# Spannungsversorgung_V2.net
KiCad netlist of a schematic drawn in EAGLE
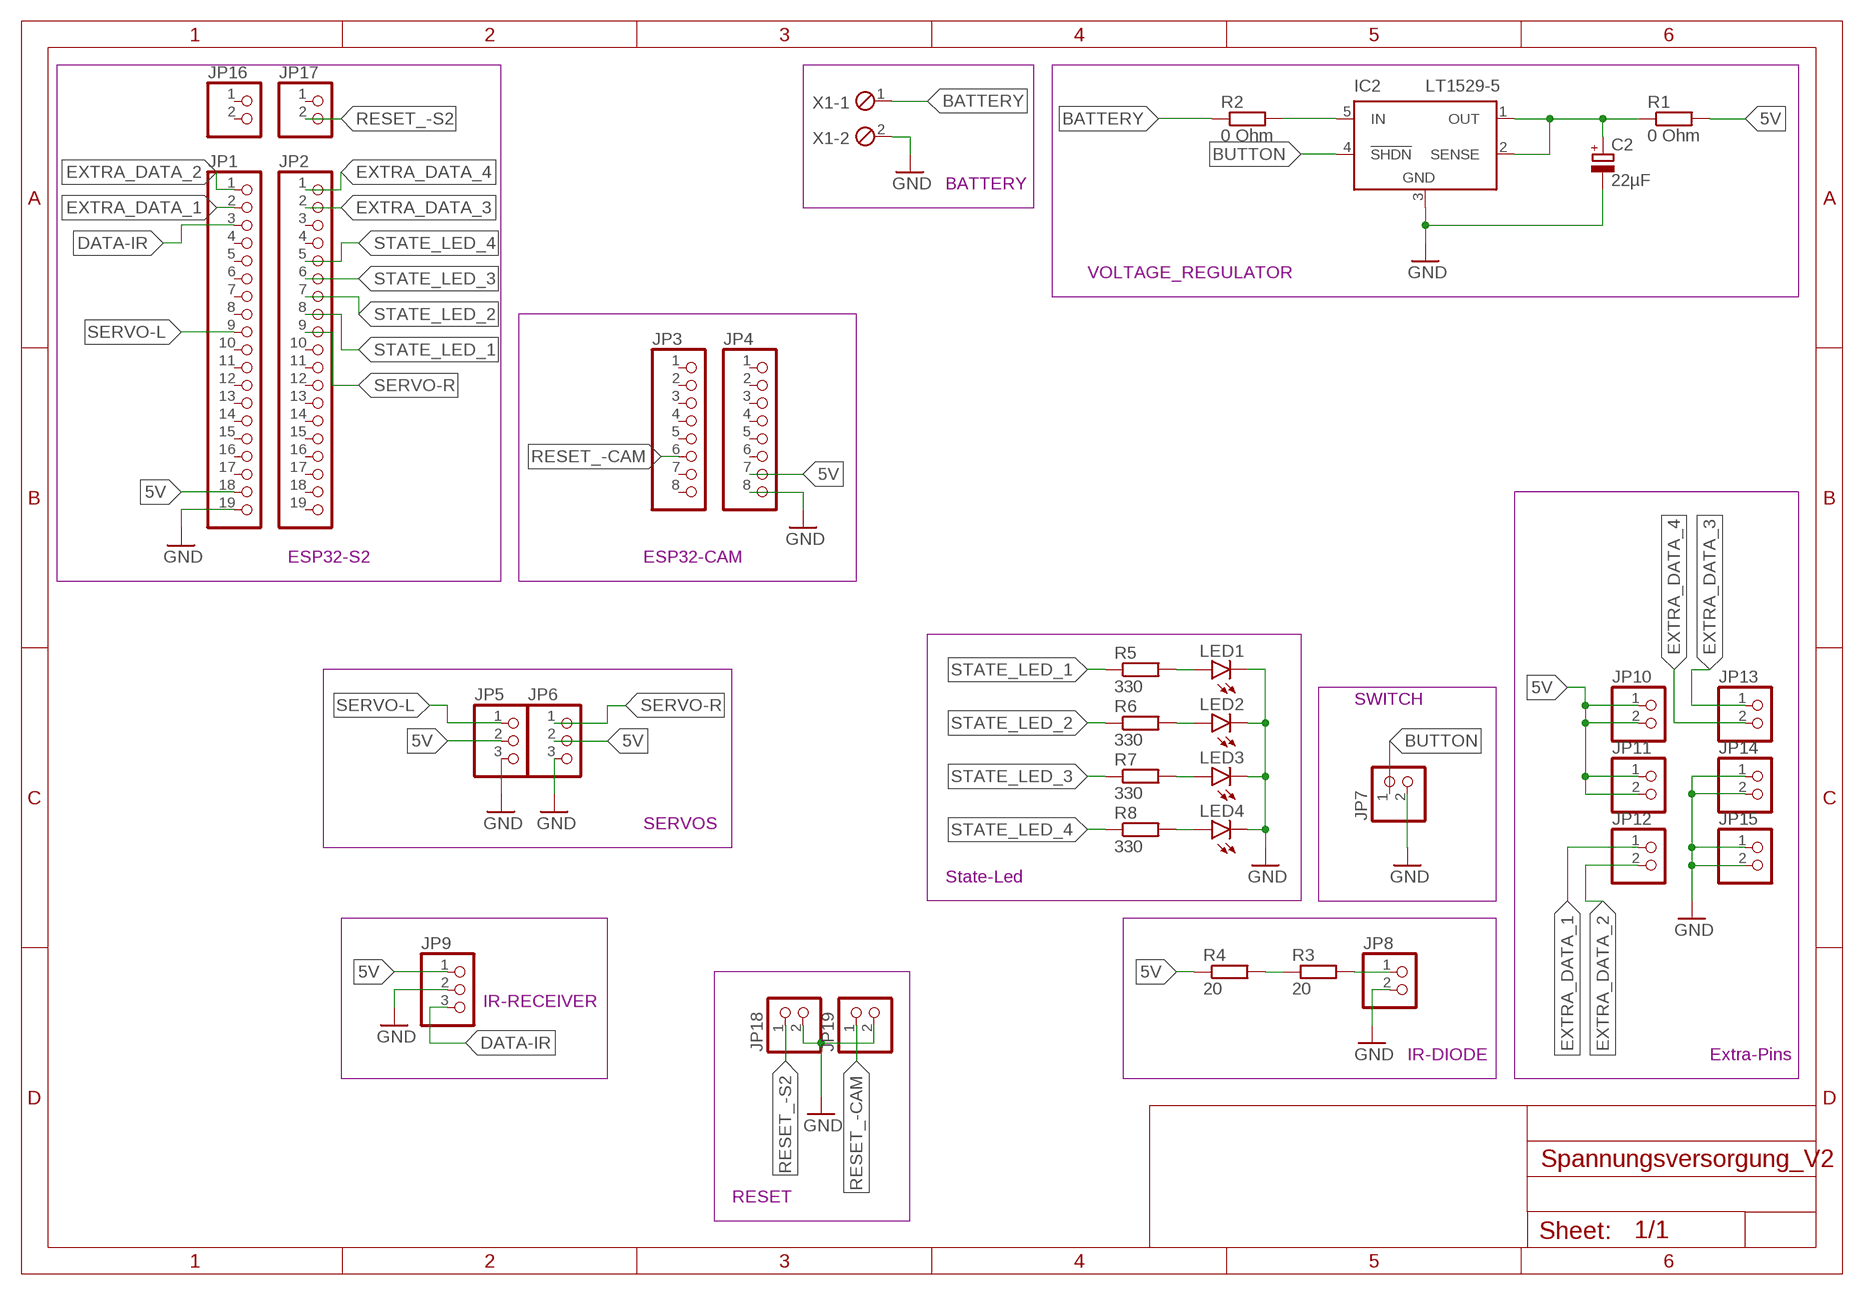
[diagram p0: schematic, sheet 1]

(export (version "E")
  (design (tool "Eeschema 10.0.6"))
  (components
    (comp (ref "C2")
      (value "22µF")
      (footprint "eagle-import:E2,5-5")
      (libsource (lib "eagle-import") (part "CPOL-EUE2.5-5"))
    )
    (comp (ref "IC2")
      (value "LT1529-5")
      (footprint "eagle-import:TO220-5")
      (libsource (lib "eagle-import") (part "LT1529T"))
    )
    (comp (ref "JP1")
      (value "PINHD-1X19")
      (footprint "eagle-import:1X19")
      (libsource (lib "eagle-import") (part "PINHD-1X19"))
    )
    (comp (ref "JP2")
      (value "PINHD-1X19")
      (footprint "eagle-import:1X19")
      (libsource (lib "eagle-import") (part "PINHD-1X19"))
    )
    (comp (ref "JP3")
      (value "PINHD-1X8")
      (footprint "eagle-import:1X08")
      (libsource (lib "eagle-import") (part "PINHD-1X8"))
    )
    (comp (ref "JP4")
      (value "PINHD-1X8")
      (footprint "eagle-import:1X08")
      (libsource (lib "eagle-import") (part "PINHD-1X8"))
    )
    (comp (ref "JP5")
      (value "PINHD-1X3")
      (footprint "eagle-import:1X03")
      (libsource (lib "eagle-import") (part "PINHD-1X3"))
    )
    (comp (ref "JP6")
      (value "PINHD-1X3")
      (footprint "eagle-import:1X03")
      (libsource (lib "eagle-import") (part "PINHD-1X3"))
    )
    (comp (ref "JP7")
      (value "PINHD-1X2")
      (footprint "eagle-import:1X02")
      (libsource (lib "eagle-import") (part "PINHD-1X2"))
    )
    (comp (ref "JP8")
      (value "PINHD-1X2")
      (footprint "eagle-import:1X02")
      (libsource (lib "eagle-import") (part "PINHD-1X2"))
    )
    (comp (ref "JP9")
      (value "PINHD-1X3")
      (footprint "eagle-import:1X03")
      (libsource (lib "eagle-import") (part "PINHD-1X3"))
    )
    (comp (ref "JP10")
      (value "PINHD-1X2")
      (footprint "eagle-import:1X02")
      (libsource (lib "eagle-import") (part "PINHD-1X2"))
    )
    (comp (ref "JP11")
      (value "PINHD-1X2")
      (footprint "eagle-import:1X02")
      (libsource (lib "eagle-import") (part "PINHD-1X2"))
    )
    (comp (ref "JP12")
      (value "PINHD-1X2")
      (footprint "eagle-import:1X02")
      (libsource (lib "eagle-import") (part "PINHD-1X2"))
    )
    (comp (ref "JP13")
      (value "PINHD-1X2")
      (footprint "eagle-import:1X02")
      (libsource (lib "eagle-import") (part "PINHD-1X2"))
    )
    (comp (ref "JP14")
      (value "PINHD-1X2")
      (footprint "eagle-import:1X02")
      (libsource (lib "eagle-import") (part "PINHD-1X2"))
    )
    (comp (ref "JP15")
      (value "PINHD-1X2")
      (footprint "eagle-import:1X02")
      (libsource (lib "eagle-import") (part "PINHD-1X2"))
    )
    (comp (ref "JP16")
      (value "PINHD-1X2")
      (footprint "eagle-import:1X02")
      (libsource (lib "eagle-import") (part "PINHD-1X2"))
    )
    (comp (ref "JP17")
      (value "PINHD-1X2")
      (footprint "eagle-import:1X02")
      (libsource (lib "eagle-import") (part "PINHD-1X2"))
    )
    (comp (ref "JP18")
      (value "PINHD-1X2")
      (footprint "eagle-import:1X02")
      (libsource (lib "eagle-import") (part "PINHD-1X2"))
    )
    (comp (ref "JP19")
      (value "PINHD-1X2")
      (footprint "eagle-import:1X02")
      (libsource (lib "eagle-import") (part "PINHD-1X2"))
    )
    (comp (ref "LED1")
      (value "LED3MM")
      (footprint "eagle-import:LED3MM")
      (libsource (lib "eagle-import") (part "LED3MM"))
    )
    (comp (ref "LED2")
      (value "LED3MM")
      (footprint "eagle-import:LED3MM")
      (libsource (lib "eagle-import") (part "LED3MM"))
    )
    (comp (ref "LED3")
      (value "LED3MM")
      (footprint "eagle-import:LED3MM")
      (libsource (lib "eagle-import") (part "LED3MM"))
    )
    (comp (ref "LED4")
      (value "LED3MM")
      (footprint "eagle-import:LED3MM")
      (libsource (lib "eagle-import") (part "LED3MM"))
    )
    (comp (ref "R1")
      (value "0 Ohm")
      (footprint "eagle-import:R0805")
      (libsource (lib "eagle-import") (part "R-EU_R0805"))
    )
    (comp (ref "R2")
      (value "0 Ohm")
      (footprint "eagle-import:R0805")
      (libsource (lib "eagle-import") (part "R-EU_R0805"))
    )
    (comp (ref "R3")
      (value "20")
      (footprint "eagle-import:0309_12")
      (libsource (lib "eagle-import") (part "R-EU_0309/12"))
    )
    (comp (ref "R4")
      (value "20")
      (footprint "eagle-import:0309_12")
      (libsource (lib "eagle-import") (part "R-EU_0309/12"))
    )
    (comp (ref "R5")
      (value "330")
      (footprint "eagle-import:R0805")
      (libsource (lib "eagle-import") (part "R-EU_R0805"))
    )
    (comp (ref "R6")
      (value "330")
      (footprint "eagle-import:R0805")
      (libsource (lib "eagle-import") (part "R-EU_R0805"))
    )
    (comp (ref "R7")
      (value "330")
      (footprint "eagle-import:R0805")
      (libsource (lib "eagle-import") (part "R-EU_R0805"))
    )
    (comp (ref "R8")
      (value "330")
      (footprint "eagle-import:R0805")
      (libsource (lib "eagle-import") (part "R-EU_R0805"))
    )
    (comp (ref "X1")
      (value "MPT2")
      (footprint "eagle-import:2POL254")
      (libsource (lib "eagle-import") (part "MPT2"))
    )
  )
  (nets
    (net (code "1") (name "5V") (class "Default")
      (node (ref "JP1") (pin "18") (pinfunction "18_18") (pintype "passive"))
      (node (ref "JP10") (pin "1") (pinfunction "1_1") (pintype "passive"))
      (node (ref "JP10") (pin "2") (pinfunction "2_2") (pintype "passive"))
      (node (ref "JP11") (pin "1") (pinfunction "1_1") (pintype "passive"))
      (node (ref "JP11") (pin "2") (pinfunction "2_2") (pintype "passive"))
      (node (ref "JP4") (pin "7") (pinfunction "7_7") (pintype "passive"))
      (node (ref "JP5") (pin "2") (pinfunction "2_2") (pintype "passive"))
      (node (ref "JP6") (pin "2") (pinfunction "2_2") (pintype "passive"))
      (node (ref "JP9") (pin "1") (pinfunction "1_1") (pintype "passive"))
      (node (ref "R1") (pin "2") (pinfunction "2_2") (pintype "passive"))
      (node (ref "R4") (pin "1") (pinfunction "1_1") (pintype "passive"))
    )
    (net (code "2") (name "BATTERY") (class "Default")
      (node (ref "R2") (pin "1") (pinfunction "1_1") (pintype "passive"))
      (node (ref "X1") (pin "1") (pinfunction "1_1") (pintype "passive"))
    )
    (net (code "3") (name "BUTTON") (class "Default")
      (node (ref "IC2") (pin "4") (pinfunction "~{SHDN}_4") (pintype "input"))
      (node (ref "JP7") (pin "1") (pinfunction "1_1") (pintype "passive"))
    )
    (net (code "4") (name "DATA-IR") (class "Default")
      (node (ref "JP1") (pin "3") (pinfunction "3_3") (pintype "passive"))
      (node (ref "JP9") (pin "3") (pinfunction "3_3") (pintype "passive"))
    )
    (net (code "5") (name "EXTRA_DATA_1") (class "Default")
      (node (ref "JP1") (pin "2") (pinfunction "2_2") (pintype "passive"))
      (node (ref "JP12") (pin "1") (pinfunction "1_1") (pintype "passive"))
    )
    (net (code "6") (name "EXTRA_DATA_2") (class "Default")
      (node (ref "JP1") (pin "1") (pinfunction "1_1") (pintype "passive"))
      (node (ref "JP12") (pin "2") (pinfunction "2_2") (pintype "passive"))
    )
    (net (code "7") (name "EXTRA_DATA_3") (class "Default")
      (node (ref "JP13") (pin "1") (pinfunction "1_1") (pintype "passive"))
      (node (ref "JP2") (pin "2") (pinfunction "2_2") (pintype "passive"))
    )
    (net (code "8") (name "EXTRA_DATA_4") (class "Default")
      (node (ref "JP13") (pin "2") (pinfunction "2_2") (pintype "passive"))
      (node (ref "JP2") (pin "1") (pinfunction "1_1") (pintype "passive"))
    )
    (net (code "9") (name "GND") (class "Default")
      (node (ref "C2") (pin "-") (pinfunction "-_-") (pintype "passive"))
      (node (ref "IC2") (pin "3") (pinfunction "GND_3") (pintype "power_in"))
      (node (ref "JP1") (pin "19") (pinfunction "19_19") (pintype "passive"))
      (node (ref "JP14") (pin "1") (pinfunction "1_1") (pintype "passive"))
      (node (ref "JP14") (pin "2") (pinfunction "2_2") (pintype "passive"))
      (node (ref "JP15") (pin "1") (pinfunction "1_1") (pintype "passive"))
      (node (ref "JP15") (pin "2") (pinfunction "2_2") (pintype "passive"))
      (node (ref "JP18") (pin "2") (pinfunction "2_2") (pintype "passive"))
      (node (ref "JP19") (pin "2") (pinfunction "2_2") (pintype "passive"))
      (node (ref "JP4") (pin "8") (pinfunction "8_8") (pintype "passive"))
      (node (ref "JP5") (pin "3") (pinfunction "3_3") (pintype "passive"))
      (node (ref "JP6") (pin "3") (pinfunction "3_3") (pintype "passive"))
      (node (ref "JP7") (pin "2") (pinfunction "2_2") (pintype "passive"))
      (node (ref "JP8") (pin "2") (pinfunction "2_2") (pintype "passive"))
      (node (ref "JP9") (pin "2") (pinfunction "2_2") (pintype "passive"))
      (node (ref "LED1") (pin "K") (pinfunction "C_K") (pintype "passive"))
      (node (ref "LED2") (pin "K") (pinfunction "C_K") (pintype "passive"))
      (node (ref "LED3") (pin "K") (pinfunction "C_K") (pintype "passive"))
      (node (ref "LED4") (pin "K") (pinfunction "C_K") (pintype "passive"))
      (node (ref "X1") (pin "2") (pinfunction "1_2") (pintype "passive"))
    )
    (net (code "10") (name "Net-(IC2-IN)") (class "Default")
      (node (ref "IC2") (pin "5") (pinfunction "IN_5") (pintype "input"))
      (node (ref "R2") (pin "2") (pinfunction "2_2") (pintype "passive"))
    )
    (net (code "11") (name "Net-(IC2-OUT)") (class "Default")
      (node (ref "C2") (pin "+") (pinfunction "+_+") (pintype "passive"))
      (node (ref "IC2") (pin "1") (pinfunction "OUT_1") (pintype "output"))
      (node (ref "IC2") (pin "2") (pinfunction "SENSE_2") (pintype "input"))
      (node (ref "R1") (pin "1") (pinfunction "1_1") (pintype "passive"))
    )
    (net (code "12") (name "Net-(JP8-Pad1)") (class "Default")
      (node (ref "JP8") (pin "1") (pinfunction "1_1") (pintype "passive"))
      (node (ref "R3") (pin "2") (pinfunction "2_2") (pintype "passive"))
    )
    (net (code "13") (name "Net-(LED1-PadA)") (class "Default")
      (node (ref "LED1") (pin "A") (pinfunction "A_A") (pintype "passive"))
      (node (ref "R5") (pin "2") (pinfunction "2_2") (pintype "passive"))
    )
    (net (code "14") (name "Net-(LED2-PadA)") (class "Default")
      (node (ref "LED2") (pin "A") (pinfunction "A_A") (pintype "passive"))
      (node (ref "R6") (pin "2") (pinfunction "2_2") (pintype "passive"))
    )
    (net (code "15") (name "Net-(LED3-PadA)") (class "Default")
      (node (ref "LED3") (pin "A") (pinfunction "A_A") (pintype "passive"))
      (node (ref "R7") (pin "2") (pinfunction "2_2") (pintype "passive"))
    )
    (net (code "16") (name "Net-(LED4-PadA)") (class "Default")
      (node (ref "LED4") (pin "A") (pinfunction "A_A") (pintype "passive"))
      (node (ref "R8") (pin "2") (pinfunction "2_2") (pintype "passive"))
    )
    (net (code "17") (name "Net-(R3-Pad1)") (class "Default")
      (node (ref "R3") (pin "1") (pinfunction "1_1") (pintype "passive"))
      (node (ref "R4") (pin "2") (pinfunction "2_2") (pintype "passive"))
    )
    (net (code "18") (name "RESET_-CAM") (class "Default")
      (node (ref "JP19") (pin "1") (pinfunction "1_1") (pintype "passive"))
      (node (ref "JP3") (pin "6") (pinfunction "6_6") (pintype "passive"))
    )
    (net (code "19") (name "RESET_-S2") (class "Default")
      (node (ref "JP17") (pin "2") (pinfunction "2_2") (pintype "passive"))
      (node (ref "JP18") (pin "1") (pinfunction "1_1") (pintype "passive"))
    )
    (net (code "20") (name "SERVO-L") (class "Default")
      (node (ref "JP1") (pin "9") (pinfunction "9_9") (pintype "passive"))
      (node (ref "JP5") (pin "1") (pinfunction "1_1") (pintype "passive"))
    )
    (net (code "21") (name "SERVO-R") (class "Default")
      (node (ref "JP2") (pin "9") (pinfunction "9_9") (pintype "passive"))
      (node (ref "JP6") (pin "1") (pinfunction "1_1") (pintype "passive"))
    )
    (net (code "22") (name "STATE_LED_1") (class "Default")
      (node (ref "JP2") (pin "8") (pinfunction "8_8") (pintype "passive"))
      (node (ref "R5") (pin "1") (pinfunction "1_1") (pintype "passive"))
    )
    (net (code "23") (name "STATE_LED_2") (class "Default")
      (node (ref "JP2") (pin "7") (pinfunction "7_7") (pintype "passive"))
      (node (ref "R6") (pin "1") (pinfunction "1_1") (pintype "passive"))
    )
    (net (code "24") (name "STATE_LED_3") (class "Default")
      (node (ref "JP2") (pin "6") (pinfunction "6_6") (pintype "passive"))
      (node (ref "R7") (pin "1") (pinfunction "1_1") (pintype "passive"))
    )
    (net (code "25") (name "STATE_LED_4") (class "Default")
      (node (ref "JP2") (pin "5") (pinfunction "5_5") (pintype "passive"))
      (node (ref "R8") (pin "1") (pinfunction "1_1") (pintype "passive"))
    )
    (net (code "26") (name "unconnected-(JP1-Pad4)") (class "Default")
      (node (ref "JP1") (pin "4") (pinfunction "4_4") (pintype "passive"))
    )
    (net (code "27") (name "unconnected-(JP1-Pad5)") (class "Default")
      (node (ref "JP1") (pin "5") (pinfunction "5_5") (pintype "passive"))
    )
    (net (code "28") (name "unconnected-(JP1-Pad6)") (class "Default")
      (node (ref "JP1") (pin "6") (pinfunction "6_6") (pintype "passive"))
    )
    (net (code "29") (name "unconnected-(JP1-Pad7)") (class "Default")
      (node (ref "JP1") (pin "7") (pinfunction "7_7") (pintype "passive"))
    )
    (net (code "30") (name "unconnected-(JP1-Pad8)") (class "Default")
      (node (ref "JP1") (pin "8") (pinfunction "8_8") (pintype "passive"))
    )
    (net (code "31") (name "unconnected-(JP1-Pad10)") (class "Default")
      (node (ref "JP1") (pin "10") (pinfunction "10_10") (pintype "passive"))
    )
    (net (code "32") (name "unconnected-(JP1-Pad11)") (class "Default")
      (node (ref "JP1") (pin "11") (pinfunction "11_11") (pintype "passive"))
    )
    (net (code "33") (name "unconnected-(JP1-Pad12)") (class "Default")
      (node (ref "JP1") (pin "12") (pinfunction "12_12") (pintype "passive"))
    )
    (net (code "34") (name "unconnected-(JP1-Pad13)") (class "Default")
      (node (ref "JP1") (pin "13") (pinfunction "13_13") (pintype "passive"))
    )
    (net (code "35") (name "unconnected-(JP1-Pad14)") (class "Default")
      (node (ref "JP1") (pin "14") (pinfunction "14_14") (pintype "passive"))
    )
    (net (code "36") (name "unconnected-(JP1-Pad15)") (class "Default")
      (node (ref "JP1") (pin "15") (pinfunction "15_15") (pintype "passive"))
    )
    (net (code "37") (name "unconnected-(JP1-Pad16)") (class "Default")
      (node (ref "JP1") (pin "16") (pinfunction "16_16") (pintype "passive"))
    )
    (net (code "38") (name "unconnected-(JP1-Pad17)") (class "Default")
      (node (ref "JP1") (pin "17") (pinfunction "17_17") (pintype "passive"))
    )
    (net (code "39") (name "unconnected-(JP2-Pad3)") (class "Default")
      (node (ref "JP2") (pin "3") (pinfunction "3_3") (pintype "passive"))
    )
    (net (code "40") (name "unconnected-(JP2-Pad4)") (class "Default")
      (node (ref "JP2") (pin "4") (pinfunction "4_4") (pintype "passive"))
    )
    (net (code "41") (name "unconnected-(JP2-Pad10)") (class "Default")
      (node (ref "JP2") (pin "10") (pinfunction "10_10") (pintype "passive"))
    )
    (net (code "42") (name "unconnected-(JP2-Pad11)") (class "Default")
      (node (ref "JP2") (pin "11") (pinfunction "11_11") (pintype "passive"))
    )
    (net (code "43") (name "unconnected-(JP2-Pad12)") (class "Default")
      (node (ref "JP2") (pin "12") (pinfunction "12_12") (pintype "passive"))
    )
    (net (code "44") (name "unconnected-(JP2-Pad13)") (class "Default")
      (node (ref "JP2") (pin "13") (pinfunction "13_13") (pintype "passive"))
    )
    (net (code "45") (name "unconnected-(JP2-Pad14)") (class "Default")
      (node (ref "JP2") (pin "14") (pinfunction "14_14") (pintype "passive"))
    )
    (net (code "46") (name "unconnected-(JP2-Pad15)") (class "Default")
      (node (ref "JP2") (pin "15") (pinfunction "15_15") (pintype "passive"))
    )
    (net (code "47") (name "unconnected-(JP2-Pad16)") (class "Default")
      (node (ref "JP2") (pin "16") (pinfunction "16_16") (pintype "passive"))
    )
    (net (code "48") (name "unconnected-(JP2-Pad17)") (class "Default")
      (node (ref "JP2") (pin "17") (pinfunction "17_17") (pintype "passive"))
    )
    (net (code "49") (name "unconnected-(JP2-Pad18)") (class "Default")
      (node (ref "JP2") (pin "18") (pinfunction "18_18") (pintype "passive"))
    )
    (net (code "50") (name "unconnected-(JP2-Pad19)") (class "Default")
      (node (ref "JP2") (pin "19") (pinfunction "19_19") (pintype "passive"))
    )
    (net (code "51") (name "unconnected-(JP3-Pad1)") (class "Default")
      (node (ref "JP3") (pin "1") (pinfunction "1_1") (pintype "passive"))
    )
    (net (code "52") (name "unconnected-(JP3-Pad2)") (class "Default")
      (node (ref "JP3") (pin "2") (pinfunction "2_2") (pintype "passive"))
    )
    (net (code "53") (name "unconnected-(JP3-Pad3)") (class "Default")
      (node (ref "JP3") (pin "3") (pinfunction "3_3") (pintype "passive"))
    )
    (net (code "54") (name "unconnected-(JP3-Pad4)") (class "Default")
      (node (ref "JP3") (pin "4") (pinfunction "4_4") (pintype "passive"))
    )
    (net (code "55") (name "unconnected-(JP3-Pad5)") (class "Default")
      (node (ref "JP3") (pin "5") (pinfunction "5_5") (pintype "passive"))
    )
    (net (code "56") (name "unconnected-(JP3-Pad7)") (class "Default")
      (node (ref "JP3") (pin "7") (pinfunction "7_7") (pintype "passive"))
    )
    (net (code "57") (name "unconnected-(JP3-Pad8)") (class "Default")
      (node (ref "JP3") (pin "8") (pinfunction "8_8") (pintype "passive"))
    )
    (net (code "58") (name "unconnected-(JP4-Pad1)") (class "Default")
      (node (ref "JP4") (pin "1") (pinfunction "1_1") (pintype "passive"))
    )
    (net (code "59") (name "unconnected-(JP4-Pad2)") (class "Default")
      (node (ref "JP4") (pin "2") (pinfunction "2_2") (pintype "passive"))
    )
    (net (code "60") (name "unconnected-(JP4-Pad3)") (class "Default")
      (node (ref "JP4") (pin "3") (pinfunction "3_3") (pintype "passive"))
    )
    (net (code "61") (name "unconnected-(JP4-Pad4)") (class "Default")
      (node (ref "JP4") (pin "4") (pinfunction "4_4") (pintype "passive"))
    )
    (net (code "62") (name "unconnected-(JP4-Pad5)") (class "Default")
      (node (ref "JP4") (pin "5") (pinfunction "5_5") (pintype "passive"))
    )
    (net (code "63") (name "unconnected-(JP4-Pad6)") (class "Default")
      (node (ref "JP4") (pin "6") (pinfunction "6_6") (pintype "passive"))
    )
    (net (code "64") (name "unconnected-(JP16-Pad1)") (class "Default")
      (node (ref "JP16") (pin "1") (pinfunction "1_1") (pintype "passive"))
    )
    (net (code "65") (name "unconnected-(JP16-Pad2)") (class "Default")
      (node (ref "JP16") (pin "2") (pinfunction "2_2") (pintype "passive"))
    )
    (net (code "66") (name "unconnected-(JP17-Pad1)") (class "Default")
      (node (ref "JP17") (pin "1") (pinfunction "1_1") (pintype "passive"))
    )
  )
)
